# STorM32_NT_logger_v12.net
KiCad netlist of a schematic drawn in EAGLE
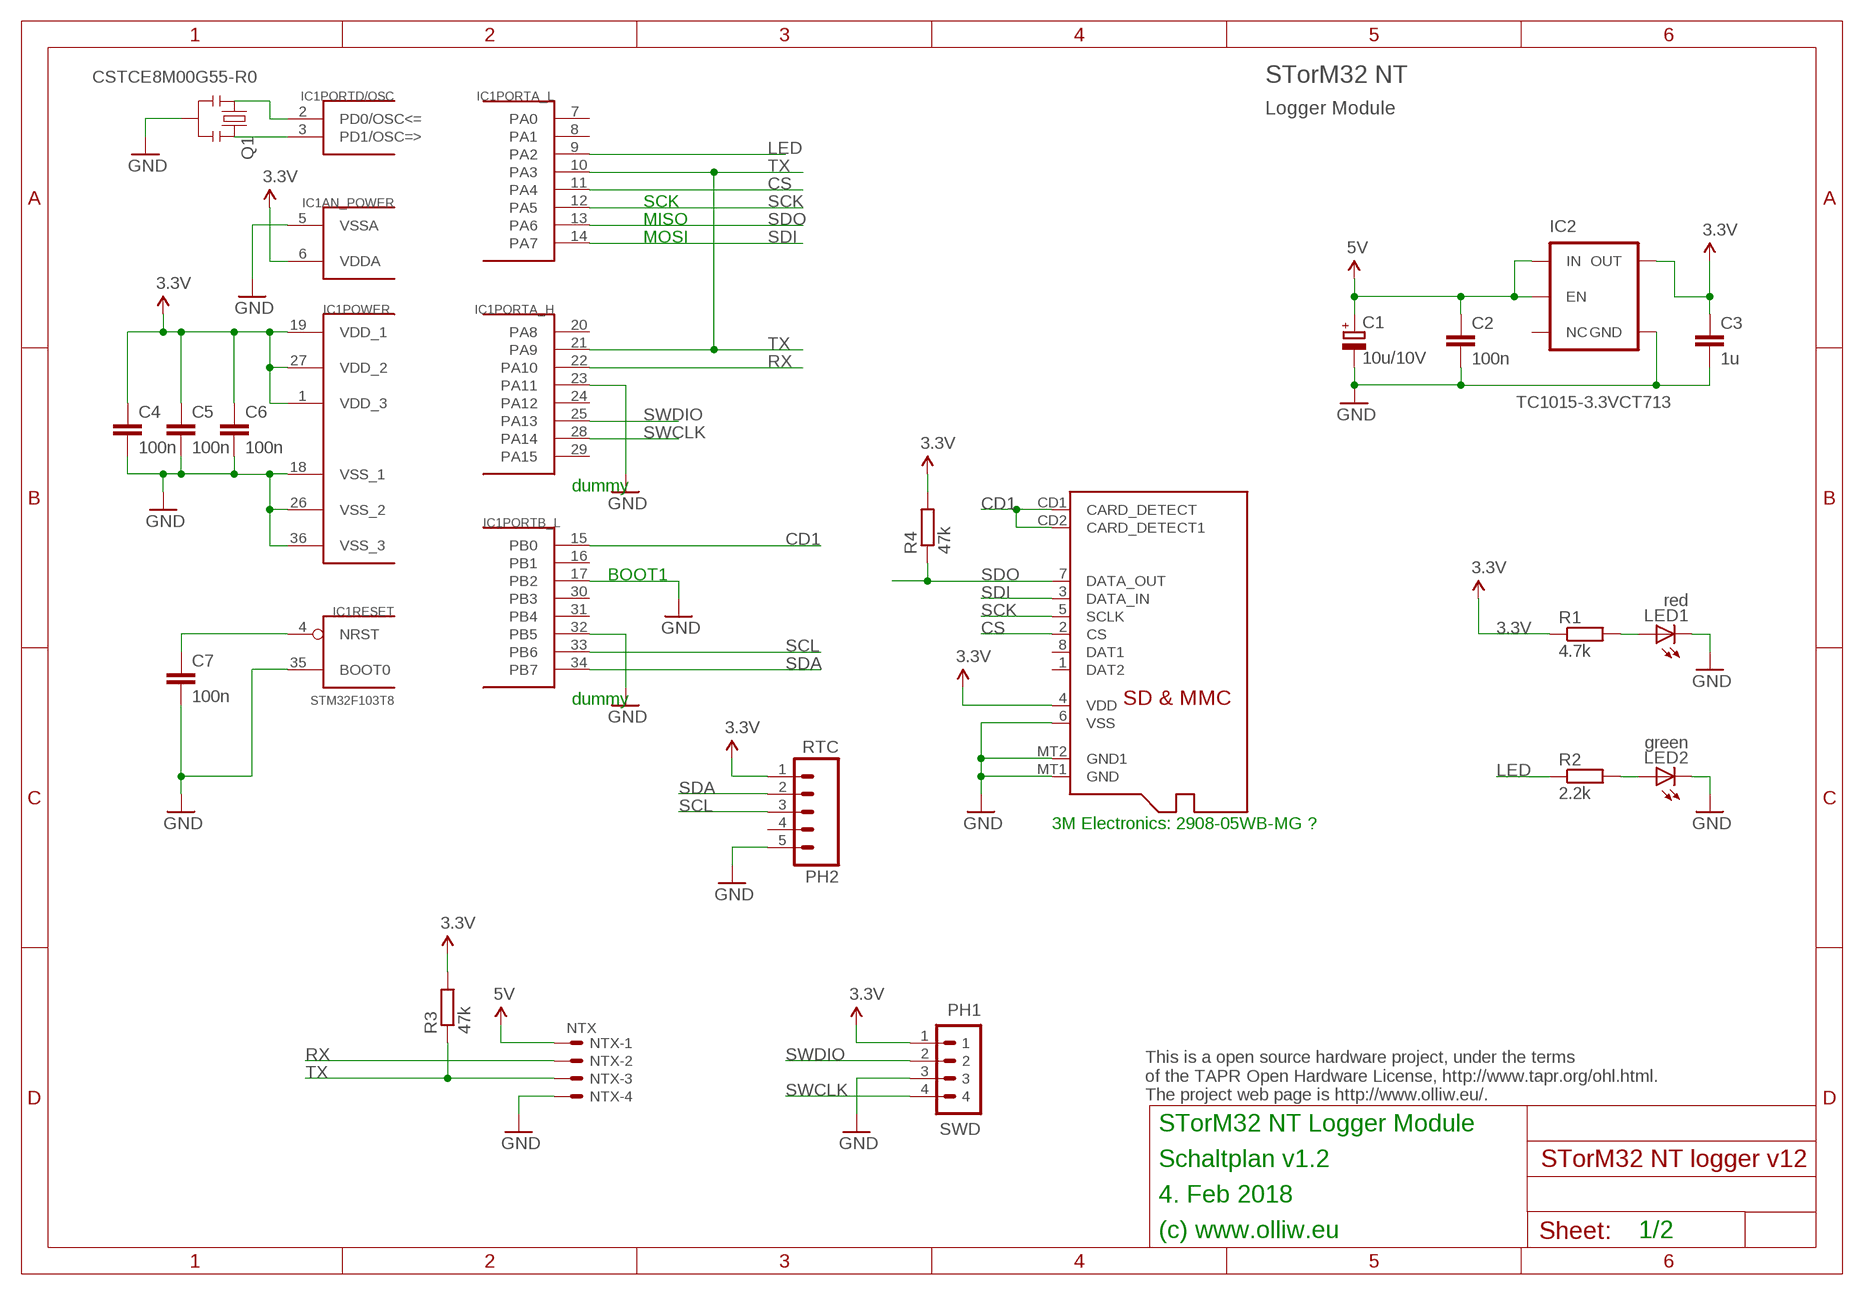
[diagram p0: schematic, sheet 1]

(export (version "E")
  (design (tool "Eeschema 10.0.6"))
  (components
    (comp (ref "C1")
      (value "10u/10V")
      (footprint "eagle-import:SMC_B")
      (libsource (lib "eagle-import") (part "CPOL-EUSMCB"))
    )
    (comp (ref "C2")
      (value "100n")
      (footprint "eagle-import:C0603")
      (libsource (lib "eagle-import") (part "C-EUC0603"))
    )
    (comp (ref "C3")
      (value "1u")
      (footprint "eagle-import:C0603")
      (libsource (lib "eagle-import") (part "C-EUC0603"))
    )
    (comp (ref "C4")
      (value "100n")
      (footprint "eagle-import:C0603")
      (libsource (lib "eagle-import") (part "C-EUC0603"))
    )
    (comp (ref "C5")
      (value "100n")
      (footprint "eagle-import:C0603")
      (libsource (lib "eagle-import") (part "C-EUC0603"))
    )
    (comp (ref "C6")
      (value "100n")
      (footprint "eagle-import:C0603")
      (libsource (lib "eagle-import") (part "C-EUC0603"))
    )
    (comp (ref "C7")
      (value "100n")
      (footprint "eagle-import:C0603")
      (libsource (lib "eagle-import") (part "C-EUC0603"))
    )
    (comp (ref "IC1")
      (value "STM32F103T8")
      (footprint "eagle-import:VFQFPN36")
      (libsource (lib "eagle-import") (part "STM32F10XTXU6"))
    )
    (comp (ref "IC2")
      (value "TC1015-3.3VCT713")
      (footprint "eagle-import:SOT23-5")
      (libsource (lib "eagle-import") (part "V_REG_TPS76433SOT23-5"))
    )
    (comp (ref "LED1")
      (value "red")
      (footprint "eagle-import:CHIPLED_0603")
      (libsource (lib "eagle-import") (part "LEDCHIPLED_0603"))
    )
    (comp (ref "LED2")
      (value "green")
      (footprint "eagle-import:CHIPLED_0603")
      (libsource (lib "eagle-import") (part "LEDCHIPLED_0603"))
    )
    (comp (ref "NTX")
      (value "NTX")
      (footprint "eagle-import:SM04B-SRSS-TB")
      (libsource (lib "eagle-import") (part "?M04B-SRSS-TBS"))
    )
    (comp (ref "PH1")
      (value "SWD")
      (footprint "eagle-import:4X1_1P27_OCT_BILEX")
      (libsource (lib "eagle-import") (part "P4X1_1P27-OCT_BILEX"))
    )
    (comp (ref "PH2")
      (value "RTC")
      (footprint "eagle-import:1X05")
      (libsource (lib "eagle-import") (part "M05PTH"))
    )
    (comp (ref "Q1")
      (value "CSTCE8M00G55-R0")
      (footprint "eagle-import:RESONATOR-SMD")
      (libsource (lib "eagle-import") (part "RESONATORSMD"))
    )
    (comp (ref "R1")
      (value "4.7k")
      (footprint "eagle-import:R0603")
      (libsource (lib "eagle-import") (part "R-EU_R0603"))
    )
    (comp (ref "R2")
      (value "2.2k")
      (footprint "eagle-import:R0603")
      (libsource (lib "eagle-import") (part "R-EU_R0603"))
    )
    (comp (ref "R3")
      (value "47k")
      (footprint "eagle-import:R0603")
      (libsource (lib "eagle-import") (part "R-EU_R0603"))
    )
    (comp (ref "R4")
      (value "47k")
      (footprint "eagle-import:R0603")
      (libsource (lib "eagle-import") (part "R-EU_R0603"))
    )
    (comp (ref "U1")
      (value "3M 2908-05WB-MG ??")
      (footprint "eagle-import:MICROSD")
      (libsource (lib "eagle-import") (part "MICROSD"))
    )
  )
  (nets
    (net (code "1") (name "/CD1") (class "Default")
      (node (ref "IC1") (pin "15") (pinfunction "PB0_15") (pintype "bidirectional"))
      (node (ref "U1") (pin "CD1") (pinfunction "CARD_DETECT_CD1") (pintype "passive"))
      (node (ref "U1") (pin "CD2") (pinfunction "CARD_DETECT1_CD2") (pintype "passive"))
    )
    (net (code "2") (name "/CS") (class "Default")
      (node (ref "IC1") (pin "11") (pinfunction "PA4_11") (pintype "bidirectional"))
      (node (ref "U1") (pin "2") (pinfunction "CS_2") (pintype "input"))
    )
    (net (code "3") (name "/LED") (class "Default")
      (node (ref "IC1") (pin "9") (pinfunction "PA2_9") (pintype "bidirectional"))
      (node (ref "R2") (pin "1") (pinfunction "1_1") (pintype "passive"))
    )
    (net (code "4") (name "/RX") (class "Default")
      (node (ref "IC1") (pin "22") (pinfunction "PA10_22") (pintype "bidirectional"))
      (node (ref "NTX") (pin "2") (pinfunction "S_2") (pintype "passive"))
    )
    (net (code "5") (name "/SCK") (class "Default")
      (node (ref "IC1") (pin "12") (pinfunction "PA5_12") (pintype "bidirectional"))
      (node (ref "U1") (pin "5") (pinfunction "SCLK_5") (pintype "input"))
    )
    (net (code "6") (name "/SCL") (class "Default")
      (node (ref "IC1") (pin "33") (pinfunction "PB6_33") (pintype "bidirectional"))
      (node (ref "PH2") (pin "3") (pinfunction "3_3") (pintype "passive"))
    )
    (net (code "7") (name "/SDA") (class "Default")
      (node (ref "IC1") (pin "34") (pinfunction "PB7_34") (pintype "bidirectional"))
      (node (ref "PH2") (pin "2") (pinfunction "2_2") (pintype "passive"))
    )
    (net (code "8") (name "/SDI") (class "Default")
      (node (ref "IC1") (pin "14") (pinfunction "PA7_14") (pintype "bidirectional"))
      (node (ref "U1") (pin "3") (pinfunction "DATA_IN_3") (pintype "input"))
    )
    (net (code "9") (name "/SDO") (class "Default")
      (node (ref "IC1") (pin "13") (pinfunction "PA6_13") (pintype "bidirectional"))
      (node (ref "R4") (pin "1") (pinfunction "1_1") (pintype "passive"))
      (node (ref "U1") (pin "7") (pinfunction "DATA_OUT_7") (pintype "output"))
    )
    (net (code "10") (name "/SWCLK") (class "Default")
      (node (ref "IC1") (pin "28") (pinfunction "PA14_28") (pintype "bidirectional"))
      (node (ref "PH1") (pin "4") (pinfunction "4_4") (pintype "passive"))
    )
    (net (code "11") (name "/SWDIO") (class "Default")
      (node (ref "IC1") (pin "25") (pinfunction "PA13_25") (pintype "bidirectional"))
      (node (ref "PH1") (pin "2") (pinfunction "2_2") (pintype "passive"))
    )
    (net (code "12") (name "/TX") (class "Default")
      (node (ref "IC1") (pin "10") (pinfunction "PA3_10") (pintype "bidirectional"))
      (node (ref "IC1") (pin "21") (pinfunction "PA9_21") (pintype "bidirectional"))
      (node (ref "NTX") (pin "3") (pinfunction "S_3") (pintype "passive"))
      (node (ref "R3") (pin "1") (pinfunction "1_1") (pintype "passive"))
    )
    (net (code "13") (name "3.3V") (class "Default")
      (node (ref "C3") (pin "1") (pinfunction "1_1") (pintype "passive"))
      (node (ref "C4") (pin "1") (pinfunction "1_1") (pintype "passive"))
      (node (ref "C5") (pin "1") (pinfunction "1_1") (pintype "passive"))
      (node (ref "C6") (pin "1") (pinfunction "1_1") (pintype "passive"))
      (node (ref "IC1") (pin "1") (pinfunction "VDD_3_1") (pintype "power_in"))
      (node (ref "IC1") (pin "19") (pinfunction "VDD_1_19") (pintype "power_in"))
      (node (ref "IC1") (pin "27") (pinfunction "VDD_2_27") (pintype "power_in"))
      (node (ref "IC1") (pin "6") (pinfunction "VDDA_6") (pintype "power_in"))
      (node (ref "IC2") (pin "5") (pinfunction "OUT_5") (pintype "passive"))
      (node (ref "PH1") (pin "1") (pinfunction "1_1") (pintype "passive"))
      (node (ref "PH2") (pin "1") (pinfunction "1_1") (pintype "passive"))
      (node (ref "R1") (pin "1") (pinfunction "1_1") (pintype "passive"))
      (node (ref "R3") (pin "2") (pinfunction "2_2") (pintype "passive"))
      (node (ref "R4") (pin "2") (pinfunction "2_2") (pintype "passive"))
      (node (ref "U1") (pin "4") (pinfunction "VDD_4") (pintype "power_in"))
    )
    (net (code "14") (name "5V") (class "Default")
      (node (ref "C1") (pin "+") (pinfunction "+_+") (pintype "passive"))
      (node (ref "C2") (pin "1") (pinfunction "1_1") (pintype "passive"))
      (node (ref "IC2") (pin "1") (pinfunction "IN_1") (pintype "input"))
      (node (ref "IC2") (pin "3") (pinfunction "EN_3") (pintype "input"))
      (node (ref "NTX") (pin "1") (pinfunction "S_1") (pintype "passive"))
    )
    (net (code "15") (name "GND") (class "Default")
      (node (ref "C1") (pin "-") (pinfunction "-_-") (pintype "passive"))
      (node (ref "C2") (pin "2") (pinfunction "2_2") (pintype "passive"))
      (node (ref "C3") (pin "2") (pinfunction "2_2") (pintype "passive"))
      (node (ref "C4") (pin "2") (pinfunction "2_2") (pintype "passive"))
      (node (ref "C5") (pin "2") (pinfunction "2_2") (pintype "passive"))
      (node (ref "C6") (pin "2") (pinfunction "2_2") (pintype "passive"))
      (node (ref "C7") (pin "2") (pinfunction "2_2") (pintype "passive"))
      (node (ref "IC1") (pin "17") (pinfunction "PB2_17") (pintype "bidirectional"))
      (node (ref "IC1") (pin "18") (pinfunction "VSS_1_18") (pintype "power_in"))
      (node (ref "IC1") (pin "23") (pinfunction "PA11_23") (pintype "bidirectional"))
      (node (ref "IC1") (pin "26") (pinfunction "VSS_2_26") (pintype "power_in"))
      (node (ref "IC1") (pin "32") (pinfunction "PB5_32") (pintype "bidirectional"))
      (node (ref "IC1") (pin "35") (pinfunction "BOOT0_35") (pintype "input"))
      (node (ref "IC1") (pin "36") (pinfunction "VSS_3_36") (pintype "power_in"))
      (node (ref "IC1") (pin "5") (pinfunction "VSSA_5") (pintype "power_in"))
      (node (ref "IC2") (pin "2") (pinfunction "GND_2") (pintype "input"))
      (node (ref "LED1") (pin "C") (pinfunction "C_C") (pintype "passive"))
      (node (ref "LED2") (pin "C") (pinfunction "C_C") (pintype "passive"))
      (node (ref "NTX") (pin "4") (pinfunction "S_4") (pintype "passive"))
      (node (ref "PH1") (pin "3") (pinfunction "3_3") (pintype "passive"))
      (node (ref "PH2") (pin "5") (pinfunction "5_5") (pintype "passive"))
      (node (ref "Q1") (pin "2") (pinfunction "2_2") (pintype "passive"))
      (node (ref "U1") (pin "6") (pinfunction "VSS_6") (pintype "power_in"))
      (node (ref "U1") (pin "MT1") (pinfunction "GND_MT1") (pintype "power_in"))
      (node (ref "U1") (pin "MT2") (pinfunction "GND1_MT2") (pintype "power_in"))
    )
    (net (code "16") (name "Net-(IC1E-PD0{slash}OSC<=)") (class "Default")
      (node (ref "IC1") (pin "2") (pinfunction "PD0/OSC<=_2") (pintype "bidirectional"))
      (node (ref "Q1") (pin "1") (pinfunction "1_1") (pintype "passive"))
    )
    (net (code "17") (name "Net-(IC1E-PD1{slash}OSC=>)") (class "Default")
      (node (ref "IC1") (pin "3") (pinfunction "PD1/OSC=>_3") (pintype "bidirectional"))
      (node (ref "Q1") (pin "3") (pinfunction "3_3") (pintype "passive"))
    )
    (net (code "18") (name "Net-(IC1G-NRST)") (class "Default")
      (node (ref "C7") (pin "1") (pinfunction "1_1") (pintype "passive"))
      (node (ref "IC1") (pin "4") (pinfunction "NRST_4") (pintype "input"))
    )
    (net (code "19") (name "Net-(LED1-PadA)") (class "Default")
      (node (ref "LED1") (pin "A") (pinfunction "A_A") (pintype "passive"))
      (node (ref "R1") (pin "2") (pinfunction "2_2") (pintype "passive"))
    )
    (net (code "20") (name "Net-(LED2-PadA)") (class "Default")
      (node (ref "LED2") (pin "A") (pinfunction "A_A") (pintype "passive"))
      (node (ref "R2") (pin "2") (pinfunction "2_2") (pintype "passive"))
    )
    (net (code "21") (name "unconnected-(IC1B-PA8-Pad20)") (class "Default")
      (node (ref "IC1") (pin "20") (pinfunction "PA8_20") (pintype "bidirectional"))
    )
    (net (code "22") (name "unconnected-(IC1B-PA12-Pad24)") (class "Default")
      (node (ref "IC1") (pin "24") (pinfunction "PA12_24") (pintype "bidirectional"))
    )
    (net (code "23") (name "unconnected-(IC1B-PA15-Pad29)") (class "Default")
      (node (ref "IC1") (pin "29") (pinfunction "PA15_29") (pintype "bidirectional"))
    )
    (net (code "24") (name "unconnected-(IC1C-PA0-Pad7)") (class "Default")
      (node (ref "IC1") (pin "7") (pinfunction "PA0_7") (pintype "bidirectional"))
    )
    (net (code "25") (name "unconnected-(IC1C-PA1-Pad8)") (class "Default")
      (node (ref "IC1") (pin "8") (pinfunction "PA1_8") (pintype "bidirectional"))
    )
    (net (code "26") (name "unconnected-(IC1D-PB1-Pad16)") (class "Default")
      (node (ref "IC1") (pin "16") (pinfunction "PB1_16") (pintype "bidirectional"))
    )
    (net (code "27") (name "unconnected-(IC1D-PB3-Pad30)") (class "Default")
      (node (ref "IC1") (pin "30") (pinfunction "PB3_30") (pintype "bidirectional"))
    )
    (net (code "28") (name "unconnected-(IC1D-PB4-Pad31)") (class "Default")
      (node (ref "IC1") (pin "31") (pinfunction "PB4_31") (pintype "bidirectional"))
    )
    (net (code "29") (name "unconnected-(IC2-NC-Pad4)") (class "Default")
      (node (ref "IC2") (pin "4") (pinfunction "NC_4") (pintype "input"))
    )
    (net (code "30") (name "unconnected-(PH2-Pad4)") (class "Default")
      (node (ref "PH2") (pin "4") (pinfunction "4_4") (pintype "passive"))
    )
    (net (code "31") (name "unconnected-(U1-DAT1-Pad8)") (class "Default")
      (node (ref "U1") (pin "8") (pinfunction "DAT1_8") (pintype "bidirectional"))
    )
    (net (code "32") (name "unconnected-(U1-DAT2-Pad1)") (class "Default")
      (node (ref "U1") (pin "1") (pinfunction "DAT2_1") (pintype "bidirectional"))
    )
  )
)
